# boost_converter_schematic.net
KiCad netlist of a schematic drawn in Altium Designer
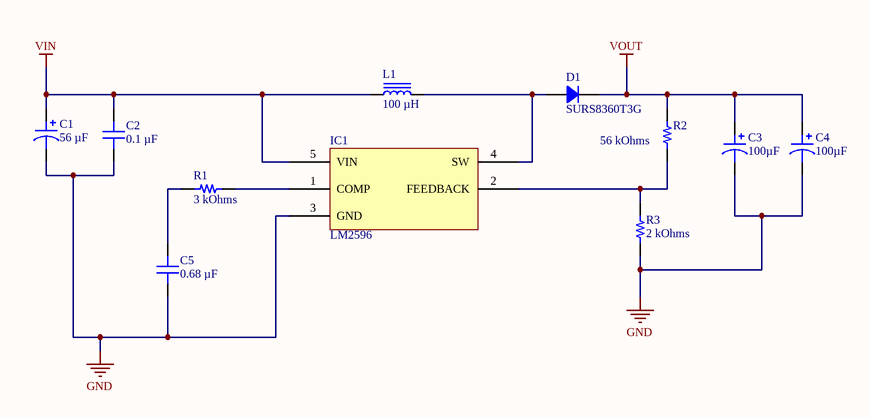
[diagram p0: boost_converter_schematic.SchDoc]

(export (version "E")
  (design (tool "Eeschema 10.0.6"))
  (components
    (comp (ref "C1")
      (value "56 µF")
      (footprint "CAP ALSMD 8.3MM H10.5MM")
      (description "CAP ALUM 56UF 20% 50V SMD")
      (fields (field (name "PART NUMBER") "865080653014") (field (name "MANUFACTURER") "Würth Elektronik"))
      (libsource (lib "Celestial Altium Library - altium_library") (part "Polarised Capacitor"))
    )
    (comp (ref "C2")
      (value "0.1 µF")
      (footprint "CAP 0805_2012")
      (description "CAP CER 0.1UF 50V X7R 0805")
      (fields (field (name "PART NUMBER") "CC0805JRX7R9BB104") (field (name "MANUFACTURER") "Yageo"))
      (libsource (lib "Celestial Altium Library - altium_library") (part "Capacitor"))
    )
    (comp (ref "C3")
      (value "100µF")
      (footprint "CAP ALSMD 8.3MM H10.5MM")
      (description "CAP ALUM 100UF 20% 50V SMD")
      (fields
        (field (name "PART NUMBER") "EEE-FK1H101P")
        (field (name "MANUFACTURER") "Panasonic Electronic Components")
      )
      (libsource (lib "Celestial Altium Library - altium_library") (part "Polarised Capacitor"))
    )
    (comp (ref "C4")
      (value "100µF")
      (footprint "CAP ALSMD 8.3MM H10.5MM")
      (description "CAP ALUM 100UF 20% 50V SMD")
      (fields
        (field (name "PART NUMBER") "EEE-FK1H101P")
        (field (name "MANUFACTURER") "Panasonic Electronic Components")
      )
      (libsource (lib "Celestial Altium Library - altium_library") (part "Polarised Capacitor"))
    )
    (comp (ref "C5")
      (value "0.68 µF")
      (footprint "CAP 0805_2012")
      (description "CAP CER 0.68UF 50V X7R 0805")
      (fields (field (name "PART NUMBER") "C0805C684K5RAC7800") (field (name "MANUFACTURER") "KEMET"))
      (libsource (lib "Celestial Altium Library - altium_library") (part "Capacitor"))
    )
    (comp (ref "D1")
      (value "SURS8360T3G")
      (footprint "DO214AB SMC")
      (description "DIODE GEN PURP 600V 3A SMC")
      (fields (field (name "MANUFACTURER") "ON Semiconductor"))
      (libsource (lib "Celestial Altium Library - altium_library") (part "Diode"))
    )
    (comp (ref "IC1")
      (value "LM2596")
      (footprint "PcbLib1:D2PAK")
      (description "REGULATOR  DC TO DC ,DUCK CONVERTER")
      (libsource (lib "Schlib1") (part "LM2596"))
    )
    (comp (ref "L1")
      (value "100 µH")
      (footprint "INDUCTOR_7447070")
      (description "FIXED IND 100UH 2.1A 150MOHM SMD")
      (fields (field (name "PART NUMBER") "SRR1280-101M") (field (name "MANUFACTURER") "Bourns Inc."))
      (libsource (lib "Celestial Altium Library - altium_library") (part "Inductor"))
    )
    (comp (ref "R1")
      (value "3 kOhms")
      (footprint "RES 0805_2012")
      (description "RES SMD 3K OHM 1% 1/8W 0805")
      (fields
        (field (name "PART NUMBER") "ERJ-6ENF3001V")
        (field (name "MANUFACTURER") "Panasonic Electronic Components")
      )
      (libsource (lib "Celestial Altium Library - altium_library") (part "Resistor"))
    )
    (comp (ref "R2")
      (value "56 kOhms")
      (footprint "RES 0805_2012")
      (description "RES 56K OHM 1% 1/8W 0805")
      (fields
        (field (name "PART NUMBER") "RMCF0805FT56K0")
        (field (name "MANUFACTURER") "Stackpole Electronics Inc")
      )
      (libsource (lib "Celestial Altium Library - altium_library") (part "Resistor"))
    )
    (comp (ref "R3")
      (value "2 kOhms")
      (footprint "RES 0805_2012")
      (description "RES SMD 2K OHM 1% 1/8W 0805")
      (fields (field (name "PART NUMBER") "AC0805FR-072KL") (field (name "MANUFACTURER") "Yageo"))
      (libsource (lib "Celestial Altium Library - altium_library") (part "Resistor"))
    )
  )
  (nets
    (net (code "1") (name "GND") (class "Default")
      (node (ref "C1") (pin "2") (pinfunction "2_2") (pintype "passive"))
      (node (ref "C2") (pin "1") (pinfunction "1_1") (pintype "passive"))
      (node (ref "C3") (pin "2") (pinfunction "2_2") (pintype "passive"))
      (node (ref "C4") (pin "2") (pinfunction "2_2") (pintype "passive"))
      (node (ref "C5") (pin "1") (pinfunction "1_1") (pintype "passive"))
      (node (ref "IC1") (pin "3") (pinfunction "GND_3") (pintype "passive"))
      (node (ref "R3") (pin "1") (pinfunction "1_1") (pintype "passive"))
    )
    (net (code "2") (name "Net-(C5-Pad2)") (class "Default")
      (node (ref "C5") (pin "2") (pinfunction "2_2") (pintype "passive"))
      (node (ref "R1") (pin "1") (pinfunction "1_1") (pintype "passive"))
    )
    (net (code "3") (name "Net-(IC1-COMP)") (class "Default")
      (node (ref "IC1") (pin "1") (pinfunction "COMP_1") (pintype "passive"))
      (node (ref "R1") (pin "2") (pinfunction "2_2") (pintype "passive"))
    )
    (net (code "4") (name "Net-(IC1-FEEDBACK)") (class "Default")
      (node (ref "IC1") (pin "2") (pinfunction "FEEDBACK_2") (pintype "passive"))
      (node (ref "R2") (pin "1") (pinfunction "1_1") (pintype "passive"))
      (node (ref "R3") (pin "2") (pinfunction "2_2") (pintype "passive"))
    )
    (net (code "5") (name "Net-(IC1-SW)") (class "Default")
      (node (ref "D1") (pin "1") (pinfunction "1_1") (pintype "passive"))
      (node (ref "IC1") (pin "4") (pinfunction "SW_4") (pintype "passive"))
      (node (ref "L1") (pin "2") (pinfunction "2_2") (pintype "passive"))
    )
    (net (code "6") (name "VIN") (class "Default")
      (node (ref "C1") (pin "1") (pinfunction "1_1") (pintype "passive"))
      (node (ref "C2") (pin "2") (pinfunction "2_2") (pintype "passive"))
      (node (ref "IC1") (pin "5") (pinfunction "VIN_5") (pintype "passive"))
      (node (ref "L1") (pin "1") (pinfunction "1_1") (pintype "passive"))
    )
    (net (code "7") (name "VOUT") (class "Default")
      (node (ref "C3") (pin "1") (pinfunction "1_1") (pintype "passive"))
      (node (ref "C4") (pin "1") (pinfunction "1_1") (pintype "passive"))
      (node (ref "D1") (pin "2") (pinfunction "2_2") (pintype "passive"))
      (node (ref "R2") (pin "2") (pinfunction "2_2") (pintype "passive"))
    )
  )
)
